# GPS.net
KiCad netlist of a schematic drawn in Altium Designer
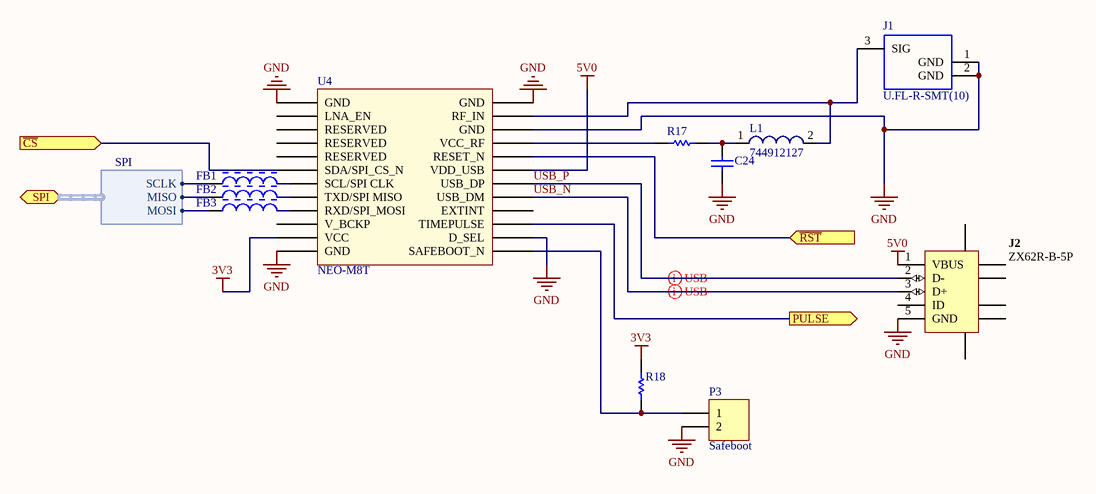
[diagram p0: GPS.SchDoc]

(export (version "E")
  (design (tool "Eeschema 10.0.6"))
  (components
    (comp (ref "C24")
      (value "CAP 10nF 10V 0603(1608)")
      (footprint "CAPC0603(1608)100_M")
      (description "CAP 10nF 10V ±10% 0603 (1608 Metric) Thickness 1mm SMD")
      (fields (field (name "TOLERANCE") "Â±10%"))
      (libsource (lib "Altium Content Vault") (part "CMP-1035-02306-1"))
    )
    (comp (ref "FB1")
      (value "BLM15HD102SN1B")
      (footprint "MURA-BLM15-CHIP-2_V")
      (fields (field (name "MANUFACTURER") "Murata"))
      (libsource (lib "Altium Content Vault") (part "CMP-0686-00278-3"))
    )
    (comp (ref "FB2")
      (value "BLM15HD102SN1B")
      (footprint "MURA-BLM15-CHIP-2_V")
      (fields (field (name "MANUFACTURER") "Murata"))
      (libsource (lib "Altium Content Vault") (part "CMP-0686-00278-3"))
    )
    (comp (ref "FB3")
      (value "BLM15HD102SN1B")
      (footprint "MURA-BLM15-CHIP-2_V")
      (fields (field (name "MANUFACTURER") "Murata"))
      (libsource (lib "Altium Content Vault") (part "CMP-0686-00278-3"))
    )
    (comp (ref "J1")
      (value "U.FL-R-SMT(10)")
      (footprint "HRS-U.FL-R-SMT_V")
      (libsource (lib "Altium Content Vault") (part "CMP-0029-00003-1"))
    )
    (comp (ref "J2")
      (value "ZX62R-B-5P")
      (footprint "HIRO-ZX62R-B-5P_V")
      (description "Connector; USBMicro-B,Reverse type, SMT; 5 Position; Right Angle")
      (libsource (lib "Altium Content Vault") (part "CMP-0031-00001-1"))
    )
    (comp (ref "L1")
      (value "744912127")
      (footprint "WE-CAIR_4248")
      (description "WE-CAIR Air Coil, L=27 nH")
      (fields (field (name "MANUFACTURER") "Wuerth Elektronik"))
      (libsource (lib "Altium Content Vault") (part "WE-IND-INDUCTOR-2"))
    )
    (comp (ref "P3")
      (value "Safeboot")
      (footprint "HDR1X2")
      (description "Header, 2-Pin")
      (fields (field (name "PUBLISHER") "Altium Limited"))
      (libsource (lib "Miscellaneous Connectors") (part "Header 2"))
    )
    (comp (ref "R17")
      (value "10R 5% 0603(1608)")
      (footprint "RESC0603(1608)_L")
      (description "10R 0.1W 5% 0603 (1608 Metric)  SMD")
      (fields (field (name "POWER") "0.1 W") (field (name "TOLERANCE") "5 %"))
      (libsource (lib "Altium Content Vault") (part "RES"))
    )
    (comp (ref "R18")
      (value "1M 5% 0603(1608)")
      (footprint "RESC0603(1608)_N")
      (description "1M 0.1W 5% 0603 (1608 Metric)  SMD")
      (fields (field (name "POWER") "0.1 W") (field (name "TOLERANCE") "5 %"))
      (libsource (lib "Altium Content Vault") (part "RES"))
    )
    (comp (ref "U4")
      (value "NEO-M8T")
      (footprint "NEO")
      (description "u-blox NEO GNSS module")
      (fields (field (name "MANUFACTURER") "u-blox"))
      (libsource (lib "ubloxLib") (part "NEO"))
    )
  )
  (nets
    (net (code "2") (name "/MISO") (class "Default")
      (node (ref "FB2") (pin "1") (pinfunction "1_1") (pintype "passive"))
    )
    (net (code "3") (name "/MOSI") (class "Default")
      (node (ref "FB3") (pin "1") (pinfunction "1_1") (pintype "passive"))
    )
    (net (code "4") (name "/PULSE") (class "Default")
      (node (ref "U4") (pin "3") (pinfunction "TIMEPULSE_3") (pintype "passive"))
    )
    (net (code "5") (name "/SCLK") (class "Default")
      (node (ref "FB1") (pin "1") (pinfunction "1_1") (pintype "passive"))
    )
    (net (code "6") (name "/USB_N") (class "Default")
      (node (ref "J2") (pin "3") (pinfunction "D+_3") (pintype "bidirectional"))
      (node (ref "U4") (pin "5") (pinfunction "USB_DM_5") (pintype "passive"))
    )
    (net (code "7") (name "/USB_P") (class "Default")
      (node (ref "J2") (pin "2") (pinfunction "D-_2") (pintype "bidirectional"))
      (node (ref "U4") (pin "6") (pinfunction "USB_DP_6") (pintype "passive"))
    )
    (net (code "9") (name "/~{CS}") (class "Default")
      (node (ref "U4") (pin "18") (pinfunction "SDA/SPI_CS_N_18") (pintype "passive"))
    )
    (net (code "10") (name "/~{RST}") (class "Default")
      (node (ref "U4") (pin "8") (pinfunction "RESET_N_8") (pintype "passive"))
    )
    (net (code "11") (name "3V3") (class "Default")
      (node (ref "R18") (pin "2") (pinfunction "2_2") (pintype "passive"))
      (node (ref "U4") (pin "23") (pinfunction "VCC_23") (pintype "passive"))
    )
    (net (code "12") (name "5V0") (class "Default")
      (node (ref "J2") (pin "1") (pinfunction "VBUS_1") (pintype "power_in"))
      (node (ref "U4") (pin "7") (pinfunction "VDD_USB_7") (pintype "passive"))
    )
    (net (code "13") (name "GND") (class "Default")
      (node (ref "C24") (pin "2") (pinfunction "2_2") (pintype "passive"))
      (node (ref "J1") (pin "1") (pinfunction "GND_1") (pintype "power_in"))
      (node (ref "J1") (pin "2") (pinfunction "GND_2") (pintype "power_in"))
      (node (ref "J2") (pin "5") (pinfunction "GND_5") (pintype "power_in"))
      (node (ref "P3") (pin "2") (pinfunction "2_2") (pintype "passive"))
      (node (ref "U4") (pin "10") (pinfunction "GND_10") (pintype "passive"))
      (node (ref "U4") (pin "12") (pinfunction "GND_12") (pintype "passive"))
      (node (ref "U4") (pin "13") (pinfunction "GND_13") (pintype "passive"))
      (node (ref "U4") (pin "2") (pinfunction "D_SEL_2") (pintype "passive"))
      (node (ref "U4") (pin "24") (pinfunction "GND_24") (pintype "passive"))
    )
    (net (code "14") (name "Net-(C24-Pad1)") (class "Default")
      (node (ref "C24") (pin "1") (pinfunction "1_1") (pintype "passive"))
      (node (ref "L1") (pin "1") (pinfunction "1_1") (pintype "passive"))
      (node (ref "R17") (pin "2") (pinfunction "2_2") (pintype "passive"))
    )
    (net (code "15") (name "Net-(J1-SIG)") (class "Default")
      (node (ref "J1") (pin "3") (pinfunction "SIG_3") (pintype "passive"))
      (node (ref "L1") (pin "2") (pinfunction "2_2") (pintype "passive"))
      (node (ref "U4") (pin "11") (pinfunction "RF_IN_11") (pintype "passive"))
    )
    (net (code "16") (name "Net-(U4-RXD{slash}SPI_MOSI)") (class "Default")
      (node (ref "FB3") (pin "2") (pinfunction "2_2") (pintype "passive"))
      (node (ref "U4") (pin "21") (pinfunction "RXD/SPI_MOSI_21") (pintype "passive"))
    )
    (net (code "17") (name "Net-(U4-SAFEBOOT_N)") (class "Default")
      (node (ref "P3") (pin "1") (pinfunction "1_1") (pintype "passive"))
      (node (ref "R18") (pin "1") (pinfunction "1_1") (pintype "passive"))
      (node (ref "U4") (pin "1") (pinfunction "SAFEBOOT_N_1") (pintype "passive"))
    )
    (net (code "18") (name "Net-(U4-SCL{slash}SPI_CLK)") (class "Default")
      (node (ref "FB1") (pin "2") (pinfunction "2_2") (pintype "passive"))
      (node (ref "U4") (pin "19") (pinfunction "SCL/SPI_CLK_19") (pintype "passive"))
    )
    (net (code "19") (name "Net-(U4-TXD{slash}SPI_MISO)") (class "Default")
      (node (ref "FB2") (pin "2") (pinfunction "2_2") (pintype "passive"))
      (node (ref "U4") (pin "20") (pinfunction "TXD/SPI_MISO_20") (pintype "passive"))
    )
    (net (code "20") (name "Net-(U4-VCC_RF)") (class "Default")
      (node (ref "R17") (pin "1") (pinfunction "1_1") (pintype "passive"))
      (node (ref "U4") (pin "9") (pinfunction "VCC_RF_9") (pintype "passive"))
    )
    (net (code "21") (name "unconnected-(J2-ID-Pad4)") (class "Default")
      (node (ref "J2") (pin "4") (pinfunction "ID_4") (pintype "passive"))
    )
    (net (code "22") (name "unconnected-(J2-SHLD-Pad6)") (class "Default")
      (node (ref "J2") (pin "6") (pinfunction "SHLD_6") (pintype "passive"))
    )
    (net (code "23") (name "unconnected-(J2-SHLD-Pad7)") (class "Default")
      (node (ref "J2") (pin "7") (pinfunction "SHLD_7") (pintype "passive"))
    )
    (net (code "24") (name "unconnected-(J2-SHLD-Pad8)") (class "Default")
      (node (ref "J2") (pin "8") (pinfunction "SHLD_8") (pintype "passive"))
    )
    (net (code "25") (name "unconnected-(J2-SHLD-Pad9)") (class "Default")
      (node (ref "J2") (pin "9") (pinfunction "SHLD_9") (pintype "passive"))
    )
    (net (code "26") (name "unconnected-(J2-SHLD-Pad10)") (class "Default")
      (node (ref "J2") (pin "10") (pinfunction "SHLD_10") (pintype "passive"))
    )
    (net (code "27") (name "unconnected-(J2-SHLD-Pad11)") (class "Default")
      (node (ref "J2") (pin "11") (pinfunction "SHLD_11") (pintype "passive"))
    )
    (net (code "28") (name "unconnected-(U4-EXTINT-Pad4)") (class "Default")
      (node (ref "U4") (pin "4") (pinfunction "EXTINT_4") (pintype "passive"))
    )
    (net (code "29") (name "unconnected-(U4-LNA_EN-Pad14)") (class "Default")
      (node (ref "U4") (pin "14") (pinfunction "LNA_EN_14") (pintype "passive"))
    )
    (net (code "30") (name "unconnected-(U4-RESERVED-Pad15)") (class "Default")
      (node (ref "U4") (pin "15") (pinfunction "RESERVED_15") (pintype "passive"))
    )
    (net (code "31") (name "unconnected-(U4-RESERVED-Pad16)") (class "Default")
      (node (ref "U4") (pin "16") (pinfunction "RESERVED_16") (pintype "passive"))
    )
    (net (code "32") (name "unconnected-(U4-RESERVED-Pad17)") (class "Default")
      (node (ref "U4") (pin "17") (pinfunction "RESERVED_17") (pintype "passive"))
    )
    (net (code "33") (name "unconnected-(U4-V_BCKP-Pad22)") (class "Default")
      (node (ref "U4") (pin "22") (pinfunction "V_BCKP_22") (pintype "passive"))
    )
  )
)
